# 8266_relay.net
KiCad netlist of a schematic drawn in EAGLE
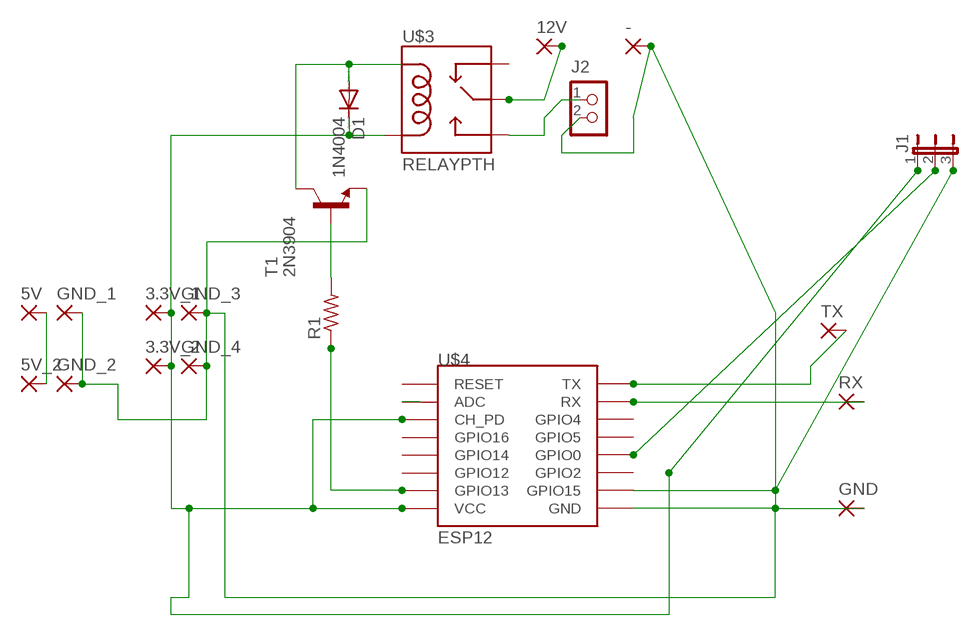
[diagram p0: schematic, sheet 1]

(export (version "E")
  (design (tool "Eeschema 10.0.6"))
  (components
    (comp (ref "-")
      (value "2,15/1,0")
      (footprint "eagle-import:2,15_1,0")
      (libsource (lib "eagle-import") (part "2,15/1,0"))
    )
    (comp (ref "3.3V_1")
      (value "2,15/1,0")
      (footprint "eagle-import:2,15_1,0")
      (libsource (lib "eagle-import") (part "2,15/1,0"))
    )
    (comp (ref "3.3V_2")
      (value "2,15/1,0")
      (footprint "eagle-import:2,15_1,0")
      (libsource (lib "eagle-import") (part "2,15/1,0"))
    )
    (comp (ref "5V")
      (value "2,15/1,0")
      (footprint "eagle-import:2,15_1,0")
      (libsource (lib "eagle-import") (part "2,15/1,0"))
    )
    (comp (ref "5V_2")
      (value "2,15/1,0")
      (footprint "eagle-import:2,15_1,0")
      (libsource (lib "eagle-import") (part "2,15/1,0"))
    )
    (comp (ref "12V")
      (value "2,15/1,0")
      (footprint "eagle-import:2,15_1,0")
      (libsource (lib "eagle-import") (part "2,15/1,0"))
    )
    (comp (ref "D1")
      (value "1N4004")
      (footprint "eagle-import:DO41-10")
      (libsource (lib "eagle-import") (part "1N4004"))
    )
    (comp (ref "GND")
      (value "2,15/1,0")
      (footprint "eagle-import:2,15_1,0")
      (libsource (lib "eagle-import") (part "2,15/1,0"))
    )
    (comp (ref "GND_1")
      (value "2,15/1,0")
      (footprint "eagle-import:2,15_1,0")
      (libsource (lib "eagle-import") (part "2,15/1,0"))
    )
    (comp (ref "GND_2")
      (value "2,15/1,0")
      (footprint "eagle-import:2,15_1,0")
      (libsource (lib "eagle-import") (part "2,15/1,0"))
    )
    (comp (ref "GND_3")
      (value "2,15/1,0")
      (footprint "eagle-import:2,15_1,0")
      (libsource (lib "eagle-import") (part "2,15/1,0"))
    )
    (comp (ref "GND_4")
      (value "2,15/1,0")
      (footprint "eagle-import:2,15_1,0")
      (libsource (lib "eagle-import") (part "2,15/1,0"))
    )
    (comp (ref "J1")
      (value "JP2E")
      (footprint "eagle-import:JP2")
      (libsource (lib "eagle-import") (part "JP2E"))
    )
    (comp (ref "J2")
      (value "CON_TERMINAL_BLOCK_02-5MM")
      (footprint "eagle-import:TERMINAL_BLOCK_2P_5")
      (libsource (lib "eagle-import") (part "CON_TERMINAL_BLOCK_02-5MM"))
    )
    (comp (ref "R1")
      (value "R-US_0309/10")
      (footprint "eagle-import:0309_10")
      (libsource (lib "eagle-import") (part "R-US_0309/10"))
    )
    (comp (ref "RX")
      (value "2,15/1,0")
      (footprint "eagle-import:2,15_1,0")
      (libsource (lib "eagle-import") (part "2,15/1,0"))
    )
    (comp (ref "T1")
      (value "2N3904")
      (footprint "eagle-import:TO92")
      (libsource (lib "eagle-import") (part "2N3904"))
    )
    (comp (ref "TX")
      (value "2,15/1,0")
      (footprint "eagle-import:2,15_1,0")
      (libsource (lib "eagle-import") (part "2,15/1,0"))
    )
    (comp (ref "U$3")
      (value "RELAYPTH")
      (footprint "eagle-import:SRD-05VDC-SL-C")
      (libsource (lib "eagle-import") (part "RELAYPTH"))
    )
    (comp (ref "U$4")
      (value "ESP12")
      (footprint "eagle-import:ESP12")
      (libsource (lib "eagle-import") (part "ESP12"))
    )
  )
  (nets
    (net (code "1") (name "Net-(--P)") (class "Default")
      (node (ref "-") (pin "1") (pinfunction "P_1") (pintype "passive"))
      (node (ref "GND") (pin "1") (pinfunction "P_1") (pintype "passive"))
      (node (ref "GND_1") (pin "1") (pinfunction "P_1") (pintype "passive"))
      (node (ref "GND_2") (pin "1") (pinfunction "P_1") (pintype "passive"))
      (node (ref "GND_3") (pin "1") (pinfunction "P_1") (pintype "passive"))
      (node (ref "GND_4") (pin "1") (pinfunction "P_1") (pintype "passive"))
      (node (ref "J1") (pin "3") (pinfunction "3_3") (pintype "passive"))
      (node (ref "J2") (pin "2") (pinfunction "2_2") (pintype "passive"))
      (node (ref "T1") (pin "3") (pinfunction "E_3") (pintype "passive"))
      (node (ref "U$4") (pin "GND") (pinfunction "GND_GND") (pintype "bidirectional"))
      (node (ref "U$4") (pin "GPIO15") (pinfunction "GPIO15_GPIO15") (pintype "bidirectional"))
    )
    (net (code "2") (name "Net-(3.3V_1-P)") (class "Default")
      (node (ref "3.3V_1") (pin "1") (pinfunction "P_1") (pintype "passive"))
      (node (ref "3.3V_2") (pin "1") (pinfunction "P_1") (pintype "passive"))
      (node (ref "D1") (pin "C") (pinfunction "C_C") (pintype "passive"))
      (node (ref "J1") (pin "1") (pinfunction "1_1") (pintype "passive"))
      (node (ref "U$3") (pin "COIL0") (pinfunction "COIL0_COIL0") (pintype "bidirectional"))
      (node (ref "U$4") (pin "CH_PD") (pinfunction "CH_PD_CH_PD") (pintype "bidirectional"))
      (node (ref "U$4") (pin "VCC") (pinfunction "VCC_VCC") (pintype "bidirectional"))
    )
    (net (code "3") (name "Net-(5V-P)") (class "Default")
      (node (ref "5V") (pin "1") (pinfunction "P_1") (pintype "passive"))
      (node (ref "5V_2") (pin "1") (pinfunction "P_1") (pintype "passive"))
    )
    (net (code "4") (name "Net-(12V-P)") (class "Default")
      (node (ref "12V") (pin "1") (pinfunction "P_1") (pintype "passive"))
      (node (ref "U$3") (pin "SWCOMMON") (pinfunction "SWCOMMON_SWCOMMON") (pintype "bidirectional"))
    )
    (net (code "5") (name "Net-(J1-Pad2)") (class "Default")
      (node (ref "J1") (pin "2") (pinfunction "2_2") (pintype "passive"))
      (node (ref "U$4") (pin "GPIO0") (pinfunction "GPIO0_GPIO0") (pintype "bidirectional"))
    )
    (net (code "6") (name "Net-(J2-Pad1)") (class "Default")
      (node (ref "J2") (pin "1") (pinfunction "1_1") (pintype "passive"))
      (node (ref "U$3") (pin "SWOPEN") (pinfunction "SWOPEN_SWOPEN") (pintype "bidirectional"))
    )
    (net (code "7") (name "Net-(R1-Pad1)") (class "Default")
      (node (ref "R1") (pin "1") (pinfunction "1_1") (pintype "passive"))
      (node (ref "U$4") (pin "GPIO13") (pinfunction "GPIO13_GPIO13") (pintype "bidirectional"))
    )
    (net (code "8") (name "Net-(RX-P)") (class "Default")
      (node (ref "RX") (pin "1") (pinfunction "P_1") (pintype "passive"))
      (node (ref "U$4") (pin "RX") (pinfunction "RX_RX") (pintype "bidirectional"))
    )
    (net (code "9") (name "Net-(T1-B)") (class "Default")
      (node (ref "R1") (pin "2") (pinfunction "2_2") (pintype "passive"))
      (node (ref "T1") (pin "2") (pinfunction "B_2") (pintype "passive"))
    )
    (net (code "10") (name "Net-(T1-C)") (class "Default")
      (node (ref "D1") (pin "A") (pinfunction "A_A") (pintype "passive"))
      (node (ref "T1") (pin "1") (pinfunction "C_1") (pintype "passive"))
      (node (ref "U$3") (pin "COIL1") (pinfunction "COIL1_COIL1") (pintype "bidirectional"))
    )
    (net (code "11") (name "Net-(TX-P)") (class "Default")
      (node (ref "TX") (pin "1") (pinfunction "P_1") (pintype "passive"))
      (node (ref "U$4") (pin "TX") (pinfunction "TX_TX") (pintype "bidirectional"))
    )
    (net (code "12") (name "unconnected-(U$3-SWCLOSE-PadSWCLOSED)") (class "Default")
      (node (ref "U$3") (pin "SWCLOSED") (pinfunction "SWCLOSE_SWCLOSED") (pintype "bidirectional"))
    )
    (net (code "13") (name "unconnected-(U$4-PadADC)") (class "Default")
      (node (ref "U$4") (pin "ADC") (pinfunction "ADC_ADC") (pintype "bidirectional"))
    )
    (net (code "14") (name "unconnected-(U$4-PadGPIO2)") (class "Default")
      (node (ref "U$4") (pin "GPIO2") (pinfunction "GPIO2_GPIO2") (pintype "bidirectional"))
    )
    (net (code "15") (name "unconnected-(U$4-PadGPIO4)") (class "Default")
      (node (ref "U$4") (pin "GPIO4") (pinfunction "GPIO4_GPIO4") (pintype "bidirectional"))
    )
    (net (code "16") (name "unconnected-(U$4-PadGPIO5)") (class "Default")
      (node (ref "U$4") (pin "GPIO5") (pinfunction "GPIO5_GPIO5") (pintype "bidirectional"))
    )
    (net (code "17") (name "unconnected-(U$4-PadGPIO12)") (class "Default")
      (node (ref "U$4") (pin "GPIO12") (pinfunction "GPIO12_GPIO12") (pintype "bidirectional"))
    )
    (net (code "18") (name "unconnected-(U$4-PadGPIO14)") (class "Default")
      (node (ref "U$4") (pin "GPIO14") (pinfunction "GPIO14_GPIO14") (pintype "bidirectional"))
    )
    (net (code "19") (name "unconnected-(U$4-PadGPIO16)") (class "Default")
      (node (ref "U$4") (pin "GPIO16") (pinfunction "GPIO16_GPIO16") (pintype "bidirectional"))
    )
    (net (code "20") (name "unconnected-(U$4-PadRESET)") (class "Default")
      (node (ref "U$4") (pin "RESET") (pinfunction "RESET_RESET") (pintype "bidirectional"))
    )
  )
)
